# S2_Sensors.net
KiCad netlist of a schematic drawn in Altium Designer
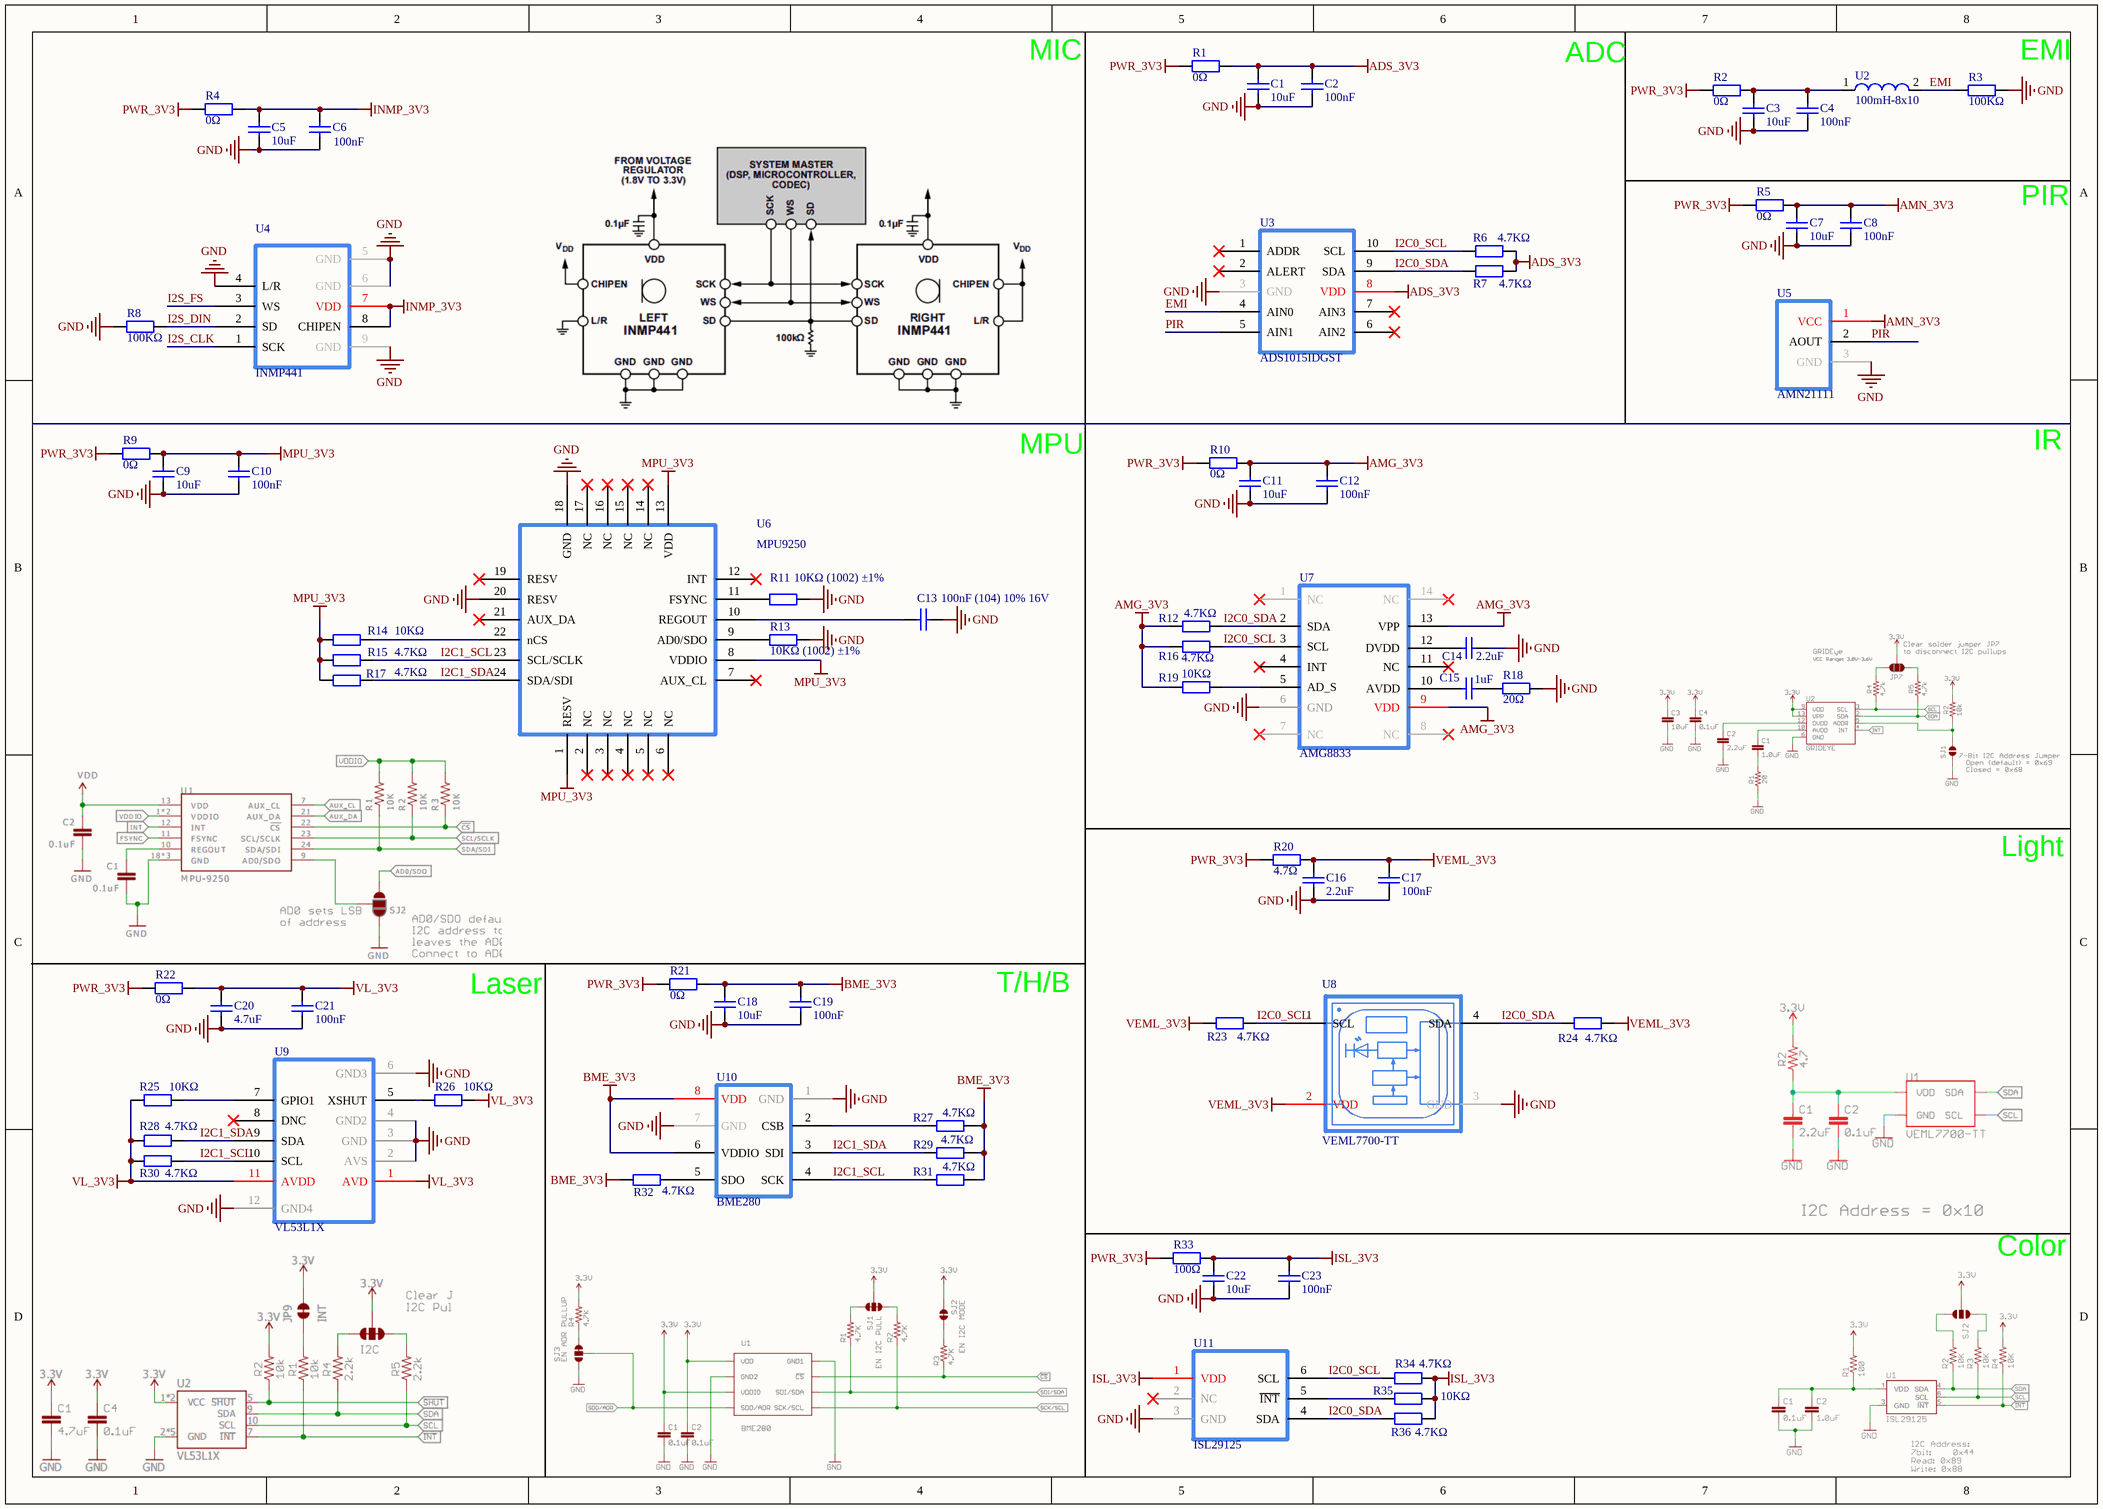
[diagram p0: S2_Sensors.SchDoc]

(export (version "E")
  (design (tool "Eeschema 10.0.6"))
  (components
    (comp (ref "C1")
      (value "10uF")
      (footprint "0402_C")
      (description "贴片电容")
      (libsource (lib "Miscellaneous Devices LC") (part "0402 10uF (106) 20% 6.3V"))
    )
    (comp (ref "C2")
      (value "100nF")
      (footprint "0402_C")
      (description "贴片电容")
      (libsource (lib "Miscellaneous Devices LC") (part "0402 100nF (104) 10% 16V"))
    )
    (comp (ref "C3")
      (value "10uF")
      (footprint "0402_C")
      (description "贴片电容")
      (libsource (lib "Miscellaneous Devices LC") (part "0402 10uF (106) 20% 6.3V"))
    )
    (comp (ref "C4")
      (value "100nF")
      (footprint "0402_C")
      (description "贴片电容")
      (libsource (lib "Miscellaneous Devices LC") (part "0402 100nF (104) 10% 16V"))
    )
    (comp (ref "C5")
      (value "10uF")
      (footprint "0402_C")
      (description "贴片电容")
      (libsource (lib "Miscellaneous Devices LC") (part "0402 10uF (106) 20% 6.3V"))
    )
    (comp (ref "C6")
      (value "100nF")
      (footprint "0402_C")
      (description "贴片电容")
      (libsource (lib "Miscellaneous Devices LC") (part "0402 100nF (104) 10% 16V"))
    )
    (comp (ref "C7")
      (value "10uF")
      (footprint "0402_C")
      (description "贴片电容")
      (libsource (lib "Miscellaneous Devices LC") (part "0402 10uF (106) 20% 6.3V"))
    )
    (comp (ref "C8")
      (value "100nF")
      (footprint "0402_C")
      (description "贴片电容")
      (libsource (lib "Miscellaneous Devices LC") (part "0402 100nF (104) 10% 16V"))
    )
    (comp (ref "C9")
      (value "10uF")
      (footprint "0402_C")
      (description "贴片电容")
      (libsource (lib "Miscellaneous Devices LC") (part "0402 10uF (106) 20% 6.3V"))
    )
    (comp (ref "C10")
      (value "100nF")
      (footprint "0402_C")
      (description "贴片电容")
      (libsource (lib "Miscellaneous Devices LC") (part "0402 100nF (104) 10% 16V"))
    )
    (comp (ref "C11")
      (value "10uF")
      (footprint "0402_C")
      (description "贴片电容")
      (libsource (lib "Miscellaneous Devices LC") (part "0402 10uF (106) 20% 6.3V"))
    )
    (comp (ref "C12")
      (value "100nF")
      (footprint "0402_C")
      (description "贴片电容")
      (libsource (lib "Miscellaneous Devices LC") (part "0402 100nF (104) 10% 16V"))
    )
    (comp (ref "C13")
      (value "100nF (104) 10% 16V")
      (footprint "0402_C")
      (description "贴片电容")
      (libsource (lib "Miscellaneous Devices LC") (part "0402 100nF (104) 10% 16V"))
    )
    (comp (ref "C14")
      (value "2.2uF")
      (footprint "0603_C")
      (description "贴片电容")
      (libsource (lib "Miscellaneous Devices LC") (part "0603 2.2uF (225) 10% 16V"))
    )
    (comp (ref "C15")
      (value "1uF")
      (footprint "0603_C")
      (description "贴片电容")
      (libsource (lib "Miscellaneous Devices LC") (part "0603 1uF (105) 10% 50V"))
    )
    (comp (ref "C16")
      (value "2.2uF")
      (footprint "0402_C")
      (description "贴片电容")
      (libsource (lib "Miscellaneous Devices LC") (part "0402 10uF (106) 20% 6.3V"))
    )
    (comp (ref "C17")
      (value "100nF")
      (footprint "0402_C")
      (description "贴片电容")
      (libsource (lib "Miscellaneous Devices LC") (part "0402 100nF (104) 10% 16V"))
    )
    (comp (ref "C18")
      (value "10uF")
      (footprint "0402_C")
      (description "贴片电容")
      (libsource (lib "Miscellaneous Devices LC") (part "0402 10uF (106) 20% 6.3V"))
    )
    (comp (ref "C19")
      (value "100nF")
      (footprint "0402_C")
      (description "贴片电容")
      (libsource (lib "Miscellaneous Devices LC") (part "0402 100nF (104) 10% 16V"))
    )
    (comp (ref "C20")
      (value "4.7uF")
      (footprint "0402_C")
      (description "贴片电容")
      (libsource (lib "Miscellaneous Devices LC") (part "0402 4.7uF (475) 20% 10V"))
    )
    (comp (ref "C21")
      (value "100nF")
      (footprint "0402_C")
      (description "贴片电容")
      (libsource (lib "Miscellaneous Devices LC") (part "0402 100nF (104) 10% 16V"))
    )
    (comp (ref "C22")
      (value "10uF")
      (footprint "0402_C")
      (description "贴片电容")
      (libsource (lib "Miscellaneous Devices LC") (part "0402 10uF (106) 20% 6.3V"))
    )
    (comp (ref "C23")
      (value "100nF")
      (footprint "0402_C")
      (description "贴片电容")
      (libsource (lib "Miscellaneous Devices LC") (part "0402 100nF (104) 10% 16V"))
    )
    (comp (ref "R1")
      (value "0Ω")
      (footprint "0402_R")
      (description "贴片电阻")
      (libsource (lib "Miscellaneous Devices LC") (part "0402 0Ω (0R0) 1%"))
    )
    (comp (ref "R2")
      (value "0Ω")
      (footprint "0402_R")
      (description "贴片电阻")
      (libsource (lib "Miscellaneous Devices LC") (part "0402 0Ω (0R0) 1%"))
    )
    (comp (ref "R3")
      (value "100KΩ")
      (footprint "0402_R")
      (description "贴片电阻")
      (libsource (lib "Miscellaneous Devices LC") (part "0402 100KΩ (1003) 1%"))
    )
    (comp (ref "R4")
      (value "0Ω")
      (footprint "0402_R")
      (description "贴片电阻")
      (libsource (lib "Miscellaneous Devices LC") (part "0402 0Ω (0R0) 1%"))
    )
    (comp (ref "R5")
      (value "0Ω")
      (footprint "0402_R")
      (description "贴片电阻")
      (libsource (lib "Miscellaneous Devices LC") (part "0402 0Ω (0R0) 1%"))
    )
    (comp (ref "R6")
      (value "4.7KΩ")
      (footprint "0402_R")
      (description "贴片电阻")
      (libsource (lib "Miscellaneous Devices LC") (part "0402 4.7KΩ (4701) 1%"))
    )
    (comp (ref "R7")
      (value "4.7KΩ")
      (footprint "0402_R")
      (description "贴片电阻")
      (libsource (lib "Miscellaneous Devices LC") (part "0402 4.7KΩ (4701) 1%"))
    )
    (comp (ref "R8")
      (value "100KΩ")
      (footprint "0402_R")
      (description "贴片电阻")
      (libsource (lib "") (part "0402 100KΩ (1003) 1%_1"))
    )
    (comp (ref "R9")
      (value "0Ω")
      (footprint "0402_R")
      (description "贴片电阻")
      (libsource (lib "Miscellaneous Devices LC") (part "0402 0Ω (0R0) 1%"))
    )
    (comp (ref "R10")
      (value "0Ω")
      (footprint "0402_R")
      (description "贴片电阻")
      (libsource (lib "Miscellaneous Devices LC") (part "0402 0Ω (0R0) 1%"))
    )
    (comp (ref "R11")
      (value "10KΩ (1002) ±1%")
      (footprint "0402_R")
      (description "贴片电阻")
      (libsource (lib "Miscellaneous Devices LC") (part "0402 10KΩ (1002) 1%"))
    )
    (comp (ref "R12")
      (value "4.7KΩ")
      (footprint "0402_R")
      (description "贴片电阻")
      (libsource (lib "Miscellaneous Devices LC") (part "0402 4.7KΩ (4701) 1%"))
    )
    (comp (ref "R13")
      (value "10KΩ (1002) ±1%")
      (footprint "0402_R")
      (description "贴片电阻")
      (libsource (lib "Miscellaneous Devices LC") (part "0402 10KΩ (1002) 1%"))
    )
    (comp (ref "R14")
      (value "10KΩ")
      (footprint "0402_R")
      (description "贴片电阻")
      (libsource (lib "Miscellaneous Devices LC") (part "0402 10KΩ (1002) 1%"))
    )
    (comp (ref "R15")
      (value "4.7KΩ")
      (footprint "0402_R")
      (description "贴片电阻")
      (libsource (lib "Miscellaneous Devices LC") (part "0402 4.7KΩ (4701) 1%"))
    )
    (comp (ref "R16")
      (value "4.7KΩ")
      (footprint "0402_R")
      (description "贴片电阻")
      (libsource (lib "Miscellaneous Devices LC") (part "0402 4.7KΩ (4701) 1%"))
    )
    (comp (ref "R17")
      (value "4.7KΩ")
      (footprint "0402_R")
      (description "贴片电阻")
      (libsource (lib "Miscellaneous Devices LC") (part "0402 4.7KΩ (4701) 1%"))
    )
    (comp (ref "R18")
      (value "20Ω")
      (footprint "0603_R")
      (description "贴片电阻")
      (libsource (lib "Miscellaneous Devices LC") (part "0603 22Ω (22R0) 1%"))
    )
    (comp (ref "R19")
      (value "10KΩ")
      (footprint "0402_R")
      (description "贴片电阻")
      (libsource (lib "Miscellaneous Devices LC") (part "0402 10KΩ (1002) 1%"))
    )
    (comp (ref "R20")
      (value "4.7Ω")
      (footprint "0402_R")
      (description "贴片电阻")
      (libsource (lib "Miscellaneous Devices LC") (part "0402 10Ω (10R0) 1%"))
    )
    (comp (ref "R21")
      (value "0Ω")
      (footprint "0402_R")
      (description "贴片电阻")
      (libsource (lib "Miscellaneous Devices LC") (part "0402 0Ω (0R0) 1%"))
    )
    (comp (ref "R22")
      (value "0Ω")
      (footprint "0402_R")
      (description "贴片电阻")
      (libsource (lib "Miscellaneous Devices LC") (part "0402 0Ω (0R0) 1%"))
    )
    (comp (ref "R23")
      (value "4.7KΩ")
      (footprint "0402_R")
      (description "贴片电阻")
      (libsource (lib "Miscellaneous Devices LC") (part "0402 4.7KΩ (4701) 1%"))
    )
    (comp (ref "R24")
      (value "4.7KΩ")
      (footprint "0402_R")
      (description "贴片电阻")
      (libsource (lib "Miscellaneous Devices LC") (part "0402 4.7KΩ (4701) 1%"))
    )
    (comp (ref "R25")
      (value "10KΩ")
      (footprint "0402_R")
      (description "贴片电阻")
      (libsource (lib "Miscellaneous Devices LC") (part "0402 10KΩ (1002) 1%"))
    )
    (comp (ref "R26")
      (value "10KΩ")
      (footprint "0402_R")
      (description "贴片电阻")
      (libsource (lib "Miscellaneous Devices LC") (part "0402 10KΩ (1002) 1%"))
    )
    (comp (ref "R27")
      (value "4.7KΩ")
      (footprint "0402_R")
      (description "贴片电阻")
      (libsource (lib "Miscellaneous Devices LC") (part "0402 4.7KΩ (4701) 1%"))
    )
    (comp (ref "R28")
      (value "4.7KΩ")
      (footprint "0402_R")
      (description "贴片电阻")
      (libsource (lib "Miscellaneous Devices LC") (part "0402 4.7KΩ (4701) 1%"))
    )
    (comp (ref "R29")
      (value "4.7KΩ")
      (footprint "0402_R")
      (description "贴片电阻")
      (libsource (lib "Miscellaneous Devices LC") (part "0402 4.7KΩ (4701) 1%"))
    )
    (comp (ref "R30")
      (value "4.7KΩ")
      (footprint "0402_R")
      (description "贴片电阻")
      (libsource (lib "Miscellaneous Devices LC") (part "0402 4.7KΩ (4701) 1%"))
    )
    (comp (ref "R31")
      (value "4.7KΩ")
      (footprint "0402_R")
      (description "贴片电阻")
      (libsource (lib "Miscellaneous Devices LC") (part "0402 4.7KΩ (4701) 1%"))
    )
    (comp (ref "R32")
      (value "4.7KΩ")
      (footprint "0402_R")
      (description "贴片电阻")
      (libsource (lib "Miscellaneous Devices LC") (part "0402 4.7KΩ (4701) 1%"))
    )
    (comp (ref "R33")
      (value "100Ω")
      (footprint "0402_R")
      (description "贴片电阻")
      (libsource (lib "Miscellaneous Devices LC") (part "0402 100Ω (1000) 1%"))
    )
    (comp (ref "R34")
      (value "4.7KΩ")
      (footprint "0402_R")
      (description "贴片电阻")
      (libsource (lib "Miscellaneous Devices LC") (part "0402 4.7KΩ (4701) 1%"))
    )
    (comp (ref "R35")
      (value "10KΩ")
      (footprint "0402_R")
      (description "贴片电阻")
      (libsource (lib "Miscellaneous Devices LC") (part "0402 10KΩ (1002) 1%"))
    )
    (comp (ref "R36")
      (value "4.7KΩ")
      (footprint "0402_R")
      (description "贴片电阻")
      (libsource (lib "Miscellaneous Devices LC") (part "0402 4.7KΩ (4701) 1%"))
    )
    (comp (ref "U2")
      (value "100mH-8x10")
      (footprint "100mH-8x10")
      (description "Sensor 100mH")
      (libsource (lib "Sensor") (part "100mH-8x10"))
    )
    (comp (ref "U3")
      (value "ADS1015IDGST")
      (footprint "ADS1015")
      (description "ADC 12Bit 4Channel")
      (fields (field (name "MF") "Texas Instruments"))
      (libsource (lib "Sensor") (part "ADS1015IDGST"))
    )
    (comp (ref "U4")
      (value "INMP441")
      (footprint "INMP441")
      (description "Sensor Microphone")
      (libsource (lib "Sensor") (part "INMP441"))
    )
    (comp (ref "U5")
      (value "AMN21111")
      (footprint "AMN21111")
      (description "Sensor PIR")
      (libsource (lib "Sensor") (part "AMN21111"))
    )
    (comp (ref "U6")
      (value "MPU9250")
      (footprint "MPU9250")
      (description "Sensor MPU")
      (libsource (lib "Sensor") (part "MPU9250"))
    )
    (comp (ref "U7")
      (value "AMG8833")
      (footprint "AMG8833")
      (description "Sensor IR")
      (libsource (lib "Sensor") (part "AMG8833"))
    )
    (comp (ref "U8")
      (value "VEML7700-TT")
      (footprint "VEML7700-TT")
      (description "Sensor Light")
      (fields (field (name "MF") "Vishay Semiconductor"))
      (libsource (lib "Sensor") (part "VEML7700-TT"))
    )
    (comp (ref "U9")
      (value "VL53L1X")
      (footprint "VL53L1X")
      (description "Sensor Laser")
      (libsource (lib "Sensor") (part "VL53L1X"))
    )
    (comp (ref "U10")
      (value "BME280")
      (footprint "BME280")
      (description "Sensor T/H/B TOP View")
      (libsource (lib "Sensor") (part "BME280"))
    )
    (comp (ref "U11")
      (value "ISL29125")
      (footprint "ISL29125")
      (description "Sensor Color")
      (libsource (lib "Sensor") (part "ISL29125"))
    )
  )
  (nets
    (net (code "1") (name "/EMI") (class "Default")
      (node (ref "R3") (pin "1") (pinfunction "1_1") (pintype "passive"))
      (node (ref "U2") (pin "2") (pinfunction "2_2") (pintype "passive"))
      (node (ref "U3") (pin "4") (pinfunction "AIN0_4") (pintype "passive"))
    )
    (net (code "2") (name "/I2C0_SCL") (class "Default")
      (node (ref "R16") (pin "2") (pinfunction "2_2") (pintype "passive"))
      (node (ref "R23") (pin "2") (pinfunction "2_2") (pintype "passive"))
      (node (ref "R34") (pin "1") (pinfunction "1_1") (pintype "passive"))
      (node (ref "R6") (pin "1") (pinfunction "1_1") (pintype "passive"))
      (node (ref "U11") (pin "6") (pinfunction "SCL_6") (pintype "passive"))
      (node (ref "U3") (pin "10") (pinfunction "SCL_10") (pintype "passive"))
      (node (ref "U7") (pin "3") (pinfunction "SCL_3") (pintype "passive"))
      (node (ref "U8") (pin "1") (pinfunction "SCL_1") (pintype "passive"))
    )
    (net (code "3") (name "/I2C0_SDA") (class "Default")
      (node (ref "R12") (pin "2") (pinfunction "2_2") (pintype "passive"))
      (node (ref "R24") (pin "1") (pinfunction "1_1") (pintype "passive"))
      (node (ref "R36") (pin "1") (pinfunction "1_1") (pintype "passive"))
      (node (ref "R7") (pin "1") (pinfunction "1_1") (pintype "passive"))
      (node (ref "U11") (pin "4") (pinfunction "SDA_4") (pintype "passive"))
      (node (ref "U3") (pin "9") (pinfunction "SDA_9") (pintype "passive"))
      (node (ref "U7") (pin "2") (pinfunction "SDA_2") (pintype "passive"))
      (node (ref "U8") (pin "4") (pinfunction "SDA_4") (pintype "passive"))
    )
    (net (code "4") (name "/I2C1_SCL") (class "Default")
      (node (ref "R15") (pin "2") (pinfunction "2_2") (pintype "passive"))
      (node (ref "R30") (pin "2") (pinfunction "2_2") (pintype "passive"))
      (node (ref "R31") (pin "1") (pinfunction "1_1") (pintype "passive"))
      (node (ref "U10") (pin "4") (pinfunction "SCK_4") (pintype "passive"))
      (node (ref "U6") (pin "23") (pinfunction "SCL/SCLK_23") (pintype "passive"))
      (node (ref "U9") (pin "10") (pinfunction "SCL_10") (pintype "passive"))
    )
    (net (code "5") (name "/I2C1_SDA") (class "Default")
      (node (ref "R17") (pin "2") (pinfunction "2_2") (pintype "passive"))
      (node (ref "R28") (pin "2") (pinfunction "2_2") (pintype "passive"))
      (node (ref "R29") (pin "1") (pinfunction "1_1") (pintype "passive"))
      (node (ref "U10") (pin "3") (pinfunction "SDI_3") (pintype "passive"))
      (node (ref "U6") (pin "24") (pinfunction "SDA/SDI_24") (pintype "passive"))
      (node (ref "U9") (pin "9") (pinfunction "SDA_9") (pintype "passive"))
    )
    (net (code "6") (name "/I2S_CLK") (class "Default")
      (node (ref "U4") (pin "1") (pinfunction "SCK_1") (pintype "passive"))
    )
    (net (code "7") (name "/I2S_DIN") (class "Default")
      (node (ref "R8") (pin "1") (pinfunction "1_1") (pintype "passive"))
      (node (ref "U4") (pin "2") (pinfunction "SD_2") (pintype "passive"))
    )
    (net (code "8") (name "/I2S_FS") (class "Default")
      (node (ref "U4") (pin "3") (pinfunction "WS_3") (pintype "passive"))
    )
    (net (code "9") (name "/PIR") (class "Default")
      (node (ref "U3") (pin "5") (pinfunction "AIN1_5") (pintype "passive"))
      (node (ref "U5") (pin "2") (pinfunction "AOUT_2") (pintype "passive"))
    )
    (net (code "10") (name "ADS_3V3") (class "Default")
      (node (ref "C1") (pin "2") (pinfunction "2_2") (pintype "passive"))
      (node (ref "C2") (pin "2") (pinfunction "2_2") (pintype "passive"))
      (node (ref "R1") (pin "2") (pinfunction "2_2") (pintype "passive"))
      (node (ref "R6") (pin "2") (pinfunction "2_2") (pintype "passive"))
      (node (ref "R7") (pin "2") (pinfunction "2_2") (pintype "passive"))
      (node (ref "U3") (pin "8") (pinfunction "VDD_8") (pintype "passive"))
    )
    (net (code "11") (name "AMG_3V3") (class "Default")
      (node (ref "C11") (pin "1") (pinfunction "1_1") (pintype "passive"))
      (node (ref "C12") (pin "1") (pinfunction "1_1") (pintype "passive"))
      (node (ref "R10") (pin "2") (pinfunction "2_2") (pintype "passive"))
      (node (ref "R12") (pin "1") (pinfunction "1_1") (pintype "passive"))
      (node (ref "R16") (pin "1") (pinfunction "1_1") (pintype "passive"))
      (node (ref "R19") (pin "1") (pinfunction "1_1") (pintype "passive"))
      (node (ref "U7") (pin "13") (pinfunction "VPP_13") (pintype "passive"))
      (node (ref "U7") (pin "9") (pinfunction "VDD_9") (pintype "passive"))
    )
    (net (code "12") (name "AMN_3V3") (class "Default")
      (node (ref "C7") (pin "2") (pinfunction "2_2") (pintype "passive"))
      (node (ref "C8") (pin "2") (pinfunction "2_2") (pintype "passive"))
      (node (ref "R5") (pin "2") (pinfunction "2_2") (pintype "passive"))
      (node (ref "U5") (pin "1") (pinfunction "VCC_1") (pintype "passive"))
    )
    (net (code "13") (name "BME_3V3") (class "Default")
      (node (ref "C18") (pin "1") (pinfunction "1_1") (pintype "passive"))
      (node (ref "C19") (pin "1") (pinfunction "1_1") (pintype "passive"))
      (node (ref "R21") (pin "2") (pinfunction "2_2") (pintype "passive"))
      (node (ref "R27") (pin "2") (pinfunction "2_2") (pintype "passive"))
      (node (ref "R29") (pin "2") (pinfunction "2_2") (pintype "passive"))
      (node (ref "R31") (pin "2") (pinfunction "2_2") (pintype "passive"))
      (node (ref "R32") (pin "1") (pinfunction "1_1") (pintype "passive"))
      (node (ref "U10") (pin "6") (pinfunction "VDDIO_6") (pintype "passive"))
      (node (ref "U10") (pin "8") (pinfunction "VDD_8") (pintype "passive"))
    )
    (net (code "14") (name "GND") (class "Default")
      (node (ref "C1") (pin "1") (pinfunction "1_1") (pintype "passive"))
      (node (ref "C10") (pin "2") (pinfunction "2_2") (pintype "passive"))
      (node (ref "C11") (pin "2") (pinfunction "2_2") (pintype "passive"))
      (node (ref "C12") (pin "2") (pinfunction "2_2") (pintype "passive"))
      (node (ref "C13") (pin "2") (pinfunction "2_2") (pintype "passive"))
      (node (ref "C14") (pin "2") (pinfunction "2_2") (pintype "passive"))
      (node (ref "C16") (pin "2") (pinfunction "2_2") (pintype "passive"))
      (node (ref "C17") (pin "2") (pinfunction "2_2") (pintype "passive"))
      (node (ref "C18") (pin "2") (pinfunction "2_2") (pintype "passive"))
      (node (ref "C19") (pin "2") (pinfunction "2_2") (pintype "passive"))
      (node (ref "C2") (pin "1") (pinfunction "1_1") (pintype "passive"))
      (node (ref "C20") (pin "1") (pinfunction "1_1") (pintype "passive"))
      (node (ref "C21") (pin "1") (pinfunction "1_1") (pintype "passive"))
      (node (ref "C22") (pin "2") (pinfunction "2_2") (pintype "passive"))
      (node (ref "C23") (pin "2") (pinfunction "2_2") (pintype "passive"))
      (node (ref "C3") (pin "1") (pinfunction "1_1") (pintype "passive"))
      (node (ref "C4") (pin "1") (pinfunction "1_1") (pintype "passive"))
      (node (ref "C5") (pin "1") (pinfunction "1_1") (pintype "passive"))
      (node (ref "C6") (pin "1") (pinfunction "1_1") (pintype "passive"))
      (node (ref "C7") (pin "1") (pinfunction "1_1") (pintype "passive"))
      (node (ref "C8") (pin "1") (pinfunction "1_1") (pintype "passive"))
      (node (ref "C9") (pin "2") (pinfunction "2_2") (pintype "passive"))
      (node (ref "R11") (pin "2") (pinfunction "2_2") (pintype "passive"))
      (node (ref "R13") (pin "2") (pinfunction "2_2") (pintype "passive"))
      (node (ref "R18") (pin "2") (pinfunction "2_2") (pintype "passive"))
      (node (ref "R3") (pin "2") (pinfunction "2_2") (pintype "passive"))
      (node (ref "R8") (pin "2") (pinfunction "2_2") (pintype "passive"))
      (node (ref "U10") (pin "1") (pinfunction "GND_1") (pintype "passive"))
      (node (ref "U10") (pin "7") (pinfunction "GND_7") (pintype "passive"))
      (node (ref "U11") (pin "3") (pinfunction "GND_3") (pintype "passive"))
      (node (ref "U3") (pin "3") (pinfunction "GND_3") (pintype "passive"))
      (node (ref "U4") (pin "4") (pinfunction "L/R_4") (pintype "passive"))
      (node (ref "U4") (pin "5") (pinfunction "GND_5") (pintype "passive"))
      (node (ref "U4") (pin "6") (pinfunction "GND_6") (pintype "passive"))
      (node (ref "U4") (pin "9") (pinfunction "GND_9") (pintype "passive"))
      (node (ref "U5") (pin "3") (pinfunction "GND_3") (pintype "passive"))
      (node (ref "U6") (pin "18") (pinfunction "GND_18") (pintype "passive"))
      (node (ref "U6") (pin "20") (pinfunction "RESV_20") (pintype "passive"))
      (node (ref "U7") (pin "6") (pinfunction "GND_6") (pintype "passive"))
      (node (ref "U8") (pin "3") (pinfunction "GND_3") (pintype "passive"))
      (node (ref "U9") (pin "12") (pinfunction "GND4_12") (pintype "passive"))
      (node (ref "U9") (pin "2") (pinfunction "AVS_2") (pintype "passive"))
      (node (ref "U9") (pin "3") (pinfunction "GND_3") (pintype "passive"))
      (node (ref "U9") (pin "4") (pinfunction "GND2_4") (pintype "passive"))
      (node (ref "U9") (pin "6") (pinfunction "GND3_6") (pintype "passive"))
    )
    (net (code "15") (name "INMP_3V3") (class "Default")
      (node (ref "C5") (pin "2") (pinfunction "2_2") (pintype "passive"))
      (node (ref "C6") (pin "2") (pinfunction "2_2") (pintype "passive"))
      (node (ref "R4") (pin "2") (pinfunction "2_2") (pintype "passive"))
      (node (ref "U4") (pin "7") (pinfunction "VDD_7") (pintype "passive"))
      (node (ref "U4") (pin "8") (pinfunction "CHIPEN_8") (pintype "passive"))
    )
    (net (code "16") (name "ISL_3V3") (class "Default")
      (node (ref "C22") (pin "1") (pinfunction "1_1") (pintype "passive"))
      (node (ref "C23") (pin "1") (pinfunction "1_1") (pintype "passive"))
      (node (ref "R33") (pin "2") (pinfunction "2_2") (pintype "passive"))
      (node (ref "R34") (pin "2") (pinfunction "2_2") (pintype "passive"))
      (node (ref "R35") (pin "2") (pinfunction "2_2") (pintype "passive"))
      (node (ref "R36") (pin "2") (pinfunction "2_2") (pintype "passive"))
      (node (ref "U11") (pin "1") (pinfunction "VDD_1") (pintype "passive"))
    )
    (net (code "17") (name "MPU_3V3") (class "Default")
      (node (ref "C10") (pin "1") (pinfunction "1_1") (pintype "passive"))
      (node (ref "C9") (pin "1") (pinfunction "1_1") (pintype "passive"))
      (node (ref "R14") (pin "1") (pinfunction "1_1") (pintype "passive"))
      (node (ref "R15") (pin "1") (pinfunction "1_1") (pintype "passive"))
      (node (ref "R17") (pin "1") (pinfunction "1_1") (pintype "passive"))
      (node (ref "R9") (pin "2") (pinfunction "2_2") (pintype "passive"))
      (node (ref "U6") (pin "1") (pinfunction "RESV_1") (pintype "passive"))
      (node (ref "U6") (pin "13") (pinfunction "VDD_13") (pintype "passive"))
      (node (ref "U6") (pin "8") (pinfunction "VDDIO_8") (pintype "passive"))
    )
    (net (code "18") (name "Net-(C3-Pad2)") (class "Default")
      (node (ref "C3") (pin "2") (pinfunction "2_2") (pintype "passive"))
      (node (ref "C4") (pin "2") (pinfunction "2_2") (pintype "passive"))
      (node (ref "R2") (pin "2") (pinfunction "2_2") (pintype "passive"))
      (node (ref "U2") (pin "1") (pinfunction "1_1") (pintype "passive"))
    )
    (net (code "19") (name "Net-(C15-Pad2)") (class "Default")
      (node (ref "C15") (pin "2") (pinfunction "2_2") (pintype "passive"))
      (node (ref "R18") (pin "1") (pinfunction "1_1") (pintype "passive"))
    )
    (net (code "20") (name "Net-(U6-AD0{slash}SDO)") (class "Default")
      (node (ref "R13") (pin "1") (pinfunction "1_1") (pintype "passive"))
      (node (ref "U6") (pin "9") (pinfunction "AD0/SDO_9") (pintype "passive"))
    )
    (net (code "21") (name "Net-(U6-FSYNC)") (class "Default")
      (node (ref "R11") (pin "1") (pinfunction "1_1") (pintype "passive"))
      (node (ref "U6") (pin "11") (pinfunction "FSYNC_11") (pintype "passive"))
    )
    (net (code "22") (name "Net-(U6-REGOUT)") (class "Default")
      (node (ref "C13") (pin "1") (pinfunction "1_1") (pintype "passive"))
      (node (ref "U6") (pin "10") (pinfunction "REGOUT_10") (pintype "passive"))
    )
    (net (code "23") (name "Net-(U6-nCS)") (class "Default")
      (node (ref "R14") (pin "2") (pinfunction "2_2") (pintype "passive"))
      (node (ref "U6") (pin "22") (pinfunction "nCS_22") (pintype "passive"))
    )
    (net (code "24") (name "Net-(U7-AD_S)") (class "Default")
      (node (ref "R19") (pin "2") (pinfunction "2_2") (pintype "passive"))
      (node (ref "U7") (pin "5") (pinfunction "AD_S_5") (pintype "passive"))
    )
    (net (code "25") (name "Net-(U7-AVDD)") (class "Default")
      (node (ref "C15") (pin "1") (pinfunction "1_1") (pintype "passive"))
      (node (ref "U7") (pin "10") (pinfunction "AVDD_10") (pintype "passive"))
    )
    (net (code "26") (name "Net-(U7-DVDD)") (class "Default")
      (node (ref "C14") (pin "1") (pinfunction "1_1") (pintype "passive"))
      (node (ref "U7") (pin "12") (pinfunction "DVDD_12") (pintype "passive"))
    )
    (net (code "27") (name "Net-(U9-GPIO1)") (class "Default")
      (node (ref "R25") (pin "2") (pinfunction "2_2") (pintype "passive"))
      (node (ref "U9") (pin "7") (pinfunction "GPIO1_7") (pintype "passive"))
    )
    (net (code "28") (name "Net-(U9-XSHUT)") (class "Default")
      (node (ref "R26") (pin "1") (pinfunction "1_1") (pintype "passive"))
      (node (ref "U9") (pin "5") (pinfunction "XSHUT_5") (pintype "passive"))
    )
    (net (code "29") (name "Net-(U10-CSB)") (class "Default")
      (node (ref "R27") (pin "1") (pinfunction "1_1") (pintype "passive"))
      (node (ref "U10") (pin "2") (pinfunction "CSB_2") (pintype "passive"))
    )
    (net (code "30") (name "Net-(U10-SDO)") (class "Default")
      (node (ref "R32") (pin "2") (pinfunction "2_2") (pintype "passive"))
      (node (ref "U10") (pin "5") (pinfunction "SDO_5") (pintype "passive"))
    )
    (net (code "31") (name "Net-(U11-~{INT})") (class "Default")
      (node (ref "R35") (pin "1") (pinfunction "1_1") (pintype "passive"))
      (node (ref "U11") (pin "5") (pinfunction "~{INT}_5") (pintype "passive"))
    )
    (net (code "32") (name "PWR_3V3") (class "Default")
      (node (ref "R1") (pin "1") (pinfunction "1_1") (pintype "passive"))
      (node (ref "R10") (pin "1") (pinfunction "1_1") (pintype "passive"))
      (node (ref "R2") (pin "1") (pinfunction "1_1") (pintype "passive"))
      (node (ref "R20") (pin "1") (pinfunction "1_1") (pintype "passive"))
      (node (ref "R21") (pin "1") (pinfunction "1_1") (pintype "passive"))
      (node (ref "R22") (pin "1") (pinfunction "1_1") (pintype "passive"))
      (node (ref "R33") (pin "1") (pinfunction "1_1") (pintype "passive"))
      (node (ref "R4") (pin "1") (pinfunction "1_1") (pintype "passive"))
      (node (ref "R5") (pin "1") (pinfunction "1_1") (pintype "passive"))
      (node (ref "R9") (pin "1") (pinfunction "1_1") (pintype "passive"))
    )
    (net (code "33") (name "VEML_3V3") (class "Default")
      (node (ref "C16") (pin "1") (pinfunction "1_1") (pintype "passive"))
      (node (ref "C17") (pin "1") (pinfunction "1_1") (pintype "passive"))
      (node (ref "R20") (pin "2") (pinfunction "2_2") (pintype "passive"))
      (node (ref "R23") (pin "1") (pinfunction "1_1") (pintype "passive"))
      (node (ref "R24") (pin "2") (pinfunction "2_2") (pintype "passive"))
      (node (ref "U8") (pin "2") (pinfunction "VDD_2") (pintype "passive"))
    )
    (net (code "34") (name "VL_3V3") (class "Default")
      (node (ref "C20") (pin "2") (pinfunction "2_2") (pintype "passive"))
      (node (ref "C21") (pin "2") (pinfunction "2_2") (pintype "passive"))
      (node (ref "R22") (pin "2") (pinfunction "2_2") (pintype "passive"))
      (node (ref "R25") (pin "1") (pinfunction "1_1") (pintype "passive"))
      (node (ref "R26") (pin "2") (pinfunction "2_2") (pintype "passive"))
      (node (ref "R28") (pin "1") (pinfunction "1_1") (pintype "passive"))
      (node (ref "R30") (pin "1") (pinfunction "1_1") (pintype "passive"))
      (node (ref "U9") (pin "1") (pinfunction "AVD_1") (pintype "passive"))
      (node (ref "U9") (pin "11") (pinfunction "AVDD_11") (pintype "passive"))
    )
    (net (code "35") (name "unconnected-(U3-ADDR-Pad1)") (class "Default")
      (node (ref "U3") (pin "1") (pinfunction "ADDR_1") (pintype "passive+no_connect"))
    )
    (net (code "36") (name "unconnected-(U3-AIN2-Pad6)") (class "Default")
      (node (ref "U3") (pin "6") (pinfunction "AIN2_6") (pintype "passive+no_connect"))
    )
    (net (code "37") (name "unconnected-(U3-AIN3-Pad7)") (class "Default")
      (node (ref "U3") (pin "7") (pinfunction "AIN3_7") (pintype "passive+no_connect"))
    )
    (net (code "38") (name "unconnected-(U3-ALERT-Pad2)") (class "Default")
      (node (ref "U3") (pin "2") (pinfunction "ALERT_2") (pintype "passive+no_connect"))
    )
    (net (code "39") (name "unconnected-(U6-AUX_CL-Pad7)") (class "Default")
      (node (ref "U6") (pin "7") (pinfunction "AUX_CL_7") (pintype "passive+no_connect"))
    )
    (net (code "40") (name "unconnected-(U6-AUX_DA-Pad21)") (class "Default")
      (node (ref "U6") (pin "21") (pinfunction "AUX_DA_21") (pintype "passive+no_connect"))
    )
    (net (code "41") (name "unconnected-(U6-INT-Pad12)") (class "Default")
      (node (ref "U6") (pin "12") (pinfunction "INT_12") (pintype "passive+no_connect"))
    )
    (net (code "42") (name "unconnected-(U6-NC-Pad2)") (class "Default")
      (node (ref "U6") (pin "2") (pinfunction "NC_2") (pintype "passive+no_connect"))
    )
    (net (code "43") (name "unconnected-(U6-NC-Pad3)") (class "Default")
      (node (ref "U6") (pin "3") (pinfunction "NC_3") (pintype "passive+no_connect"))
    )
    (net (code "44") (name "unconnected-(U6-NC-Pad4)") (class "Default")
      (node (ref "U6") (pin "4") (pinfunction "NC_4") (pintype "passive+no_connect"))
    )
    (net (code "45") (name "unconnected-(U6-NC-Pad5)") (class "Default")
      (node (ref "U6") (pin "5") (pinfunction "NC_5") (pintype "passive+no_connect"))
    )
    (net (code "46") (name "unconnected-(U6-NC-Pad6)") (class "Default")
      (node (ref "U6") (pin "6") (pinfunction "NC_6") (pintype "passive+no_connect"))
    )
    (net (code "47") (name "unconnected-(U6-NC-Pad14)") (class "Default")
      (node (ref "U6") (pin "14") (pinfunction "NC_14") (pintype "passive+no_connect"))
    )
    (net (code "48") (name "unconnected-(U6-NC-Pad15)") (class "Default")
      (node (ref "U6") (pin "15") (pinfunction "NC_15") (pintype "passive+no_connect"))
    )
    (net (code "49") (name "unconnected-(U6-NC-Pad16)") (class "Default")
      (node (ref "U6") (pin "16") (pinfunction "NC_16") (pintype "passive+no_connect"))
    )
    (net (code "50") (name "unconnected-(U6-NC-Pad17)") (class "Default")
      (node (ref "U6") (pin "17") (pinfunction "NC_17") (pintype "passive+no_connect"))
    )
    (net (code "51") (name "unconnected-(U6-RESV-Pad19)") (class "Default")
      (node (ref "U6") (pin "19") (pinfunction "RESV_19") (pintype "passive+no_connect"))
    )
    (net (code "52") (name "unconnected-(U7-INT-Pad4)") (class "Default")
      (node (ref "U7") (pin "4") (pinfunction "INT_4") (pintype "passive+no_connect"))
    )
    (net (code "53") (name "unconnected-(U7-NC-Pad1)") (class "Default")
      (node (ref "U7") (pin "1") (pinfunction "NC_1") (pintype "passive+no_connect"))
    )
    (net (code "54") (name "unconnected-(U7-NC-Pad7)") (class "Default")
      (node (ref "U7") (pin "7") (pinfunction "NC_7") (pintype "passive+no_connect"))
    )
    (net (code "55") (name "unconnected-(U7-NC-Pad8)") (class "Default")
      (node (ref "U7") (pin "8") (pinfunction "NC_8") (pintype "passive+no_connect"))
    )
    (net (code "56") (name "unconnected-(U7-NC-Pad11)") (class "Default")
      (node (ref "U7") (pin "11") (pinfunction "NC_11") (pintype "passive+no_connect"))
    )
    (net (code "57") (name "unconnected-(U7-NC-Pad14)") (class "Default")
      (node (ref "U7") (pin "14") (pinfunction "NC_14") (pintype "passive+no_connect"))
    )
    (net (code "58") (name "unconnected-(U9-DNC-Pad8)") (class "Default")
      (node (ref "U9") (pin "8") (pinfunction "DNC_8") (pintype "passive+no_connect"))
    )
    (net (code "59") (name "unconnected-(U11-NC-Pad2)") (class "Default")
      (node (ref "U11") (pin "2") (pinfunction "NC_2") (pintype "passive+no_connect"))
    )
  )
)
